# RFID_transmitter_V2.net
KiCad netlist of a schematic drawn in Altium Designer
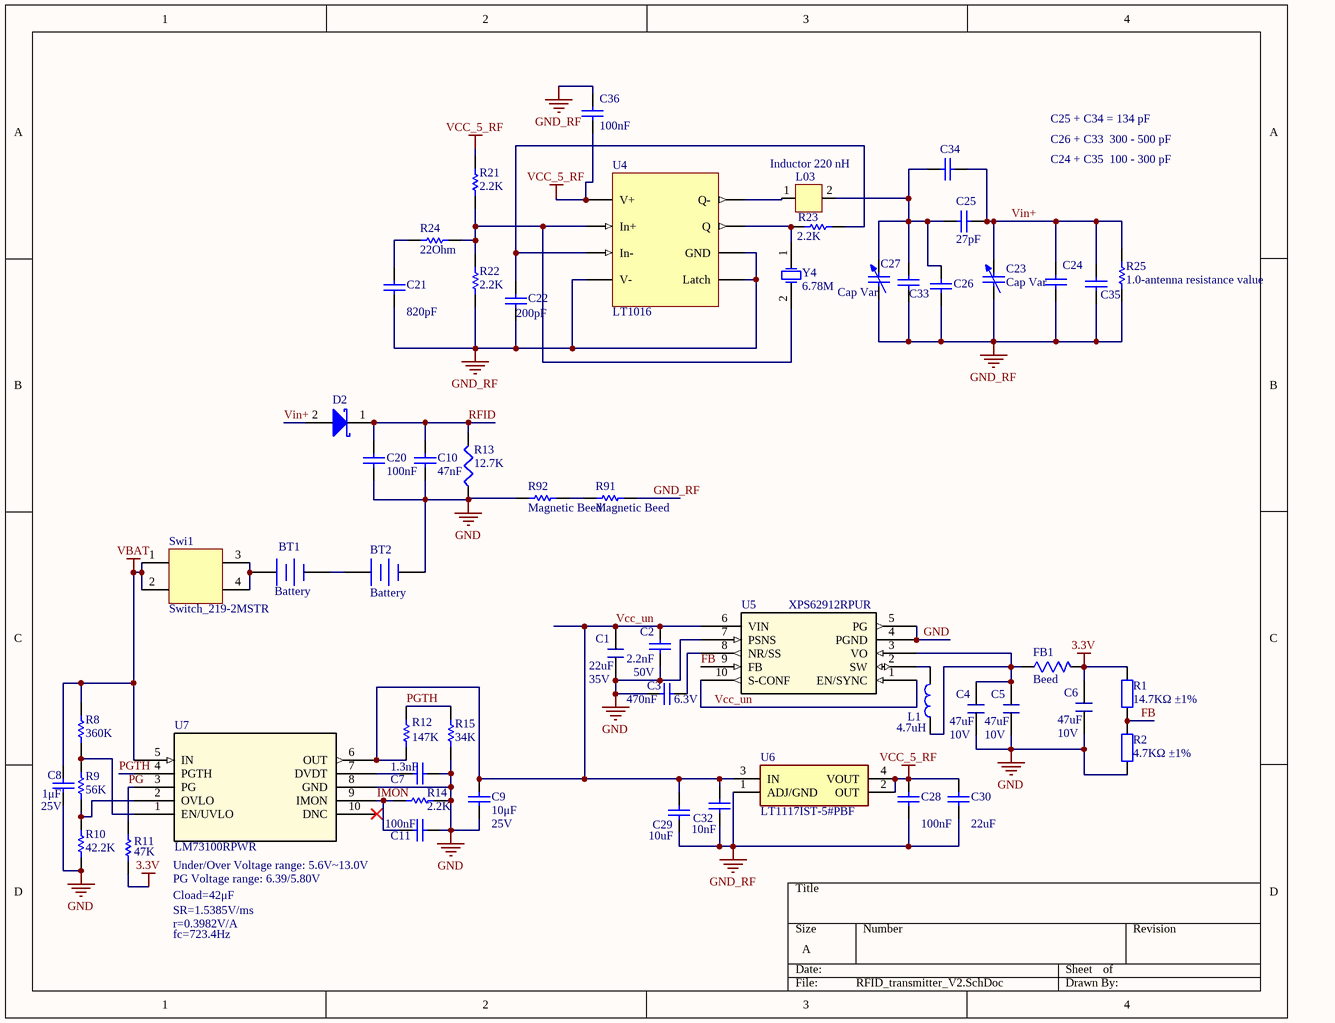
[diagram p0: RFID_transmitter_V2.SchDoc]

(export (version "E")
  (design (tool "Eeschema 10.0.6"))
  (components
    (comp (ref "BT1")
      (value "Battery")
      (footprint "Battery")
      (description "Multicell Battery")
      (fields (field (name "PUBLISHER") "Altium Limited"))
      (libsource (lib "Miscellaneous Devices") (part "Battery"))
    )
    (comp (ref "BT2")
      (value "Battery")
      (footprint "Battery")
      (description "Multicell Battery")
      (fields (field (name "PUBLISHER") "Altium Limited"))
      (libsource (lib "Miscellaneous Devices") (part "Battery"))
    )
    (comp (ref "C1")
      (value "22uF")
      (footprint "C0805")
      (fields
        (field (name "VOLTAGE") "35V")
        (field (name "PART NUMBER") "C2012X5R1V226M125AC")
        (field (name "MANUFACTURER") "TDK")
        (field (name "Comment") "Multilayer Ceramic Capacitor")
      )
      (libsource (lib "Integrated_Library") (part "C-Ceramic"))
    )
    (comp (ref "C2")
      (value "2.2nF")
      (footprint "0402")
      (description "Capacitor (Semiconductor SIM Model)")
      (fields
        (field (name "VOLTAGE") "50V")
        (field (name "PART NUMBER") "GRM155R71H222KA01D")
        (field (name "MANUFACTURER") "MuRata")
        (field (name "PUBLISHER") "Altium Limited")
      )
      (libsource (lib "Miscellaneous Devices") (part "Cap Semi"))
    )
    (comp (ref "C3")
      (value "470nF")
      (footprint "1608[0603]")
      (description "Capacitor (Semiconductor SIM Model)")
      (fields
        (field (name "VOLTAGE") "6.3V")
        (field (name "MANUFACTURER") "MuRata")
        (field (name "PART NUMBER") "GRM188R60J474KA01D")
        (field (name "PUBLISHER") "Altium Limited")
      )
      (libsource (lib "Miscellaneous Devices") (part "Cap Semi"))
    )
    (comp (ref "C4")
      (value "47uF")
      (footprint "C0805")
      (fields
        (field (name "VOLTAGE") "10V")
        (field (name "PART NUMBER") "C2012X5R1A476M125AC")
        (field (name "MANUFACTURER") "TDK")
        (field (name "Comment") "Multilayer Ceramic Capacitor")
      )
      (libsource (lib "Integrated_Library") (part "C-Ceramic"))
    )
    (comp (ref "C5")
      (value "47uF")
      (footprint "C0805")
      (fields
        (field (name "VOLTAGE") "10V")
        (field (name "PART NUMBER") "C2012X5R1A476M125AC")
        (field (name "MANUFACTURER") "TDK")
        (field (name "Comment") "Multilayer Ceramic Capacitor")
      )
      (libsource (lib "Integrated_Library") (part "C-Ceramic"))
    )
    (comp (ref "C6")
      (value "47uF")
      (footprint "C0805")
      (fields
        (field (name "VOLTAGE") "10V")
        (field (name "PART NUMBER") "C2012X5R1A476M125AC")
        (field (name "MANUFACTURER") "TDK")
        (field (name "Comment") "Multilayer Ceramic Capacitor")
      )
      (libsource (lib "Integrated_Library") (part "C-Ceramic"))
    )
    (comp (ref "C7")
      (value "1.3nF")
      (footprint "0402")
      (description "多层陶瓷电容器MLCC - SMD/SMT 1.3nF 50VDC X7R 5% 0402")
      (fields
        (field (name "VOLTAGE") "50V")
        (field (name "PART NUMBER") "GRM155R71H132JA01D")
        (field (name "PUBLISHER") "Altium Limited")
      )
      (libsource (lib "Miscellaneous Devices") (part "Cap Semi"))
    )
    (comp (ref "C8")
      (value "1μF")
      (footprint "0603")
      (description "多层陶瓷电容器MLCC - SMD/SMT 0603 1uF 25V X6S 10%")
      (fields
        (field (name "VOLTAGE") "25V")
        (field (name "MANUFACTURER") "MuRata")
        (field (name "PART NUMBER") "GRM188C81E105KAADD")
        (field (name "PUBLISHER") "Altium Limited")
      )
      (libsource (lib "Miscellaneous Devices") (part "Cap Semi"))
    )
    (comp (ref "C9")
      (value "10μF")
      (footprint "0603")
      (description "多层陶瓷电容器MLCC - SMD/SMT 10UF 25V 10% 0603")
      (fields
        (field (name "VOLTAGE") "25V")
        (field (name "MANUFACTURER") "MuRata")
        (field (name "PART NUMBER") "GRM188R61E106KA73D")
        (field (name "PUBLISHER") "Altium Limited")
      )
      (libsource (lib "Miscellaneous Devices") (part "Cap Semi"))
    )
    (comp (ref "C10")
      (value "47nF")
      (footprint "0603")
      (description "Capacitor")
      (fields
        (field (name "VOLTAGE") "50V")
        (field (name "PART NUMBER") "CL10B473KB8NNNC")
        (field (name "PUBLISHER") "Altium Limited")
      )
      (libsource (lib "Miscellaneous Devices") (part "Cap Semi"))
    )
    (comp (ref "C11")
      (value "100nF")
      (footprint "0402")
      (description "多层陶瓷电容器MLCC - SMD/SMT 100nF 10VDC X5R 5% 0402")
      (fields
        (field (name "VOLTAGE") "10V")
        (field (name "PART NUMBER") "GRM155R61A104JA01D")
        (field (name "PUBLISHER") "Altium Limited")
      )
      (libsource (lib "Miscellaneous Devices") (part "Cap Semi"))
    )
    (comp (ref "C20")
      (value "100nF")
      (footprint "0603")
      (description "Capacitor")
      (fields
        (field (name "VOLTAGE") "50V")
        (field (name "PART NUMBER") "CL10B104KB8NNNC")
        (field (name "PUBLISHER") "Altium Limited")
      )
      (libsource (lib "Miscellaneous Devices") (part "Cap Semi"))
    )
    (comp (ref "C21")
      (value "820pF")
      (footprint "0603")
      (description "Capacitor")
      (fields (field (name "Comment") "Cap 820p") (field (name "PUBLISHER") "Altium Limited"))
      (libsource (lib "Miscellaneous Devices") (part "Cap"))
    )
    (comp (ref "C22")
      (value "200pF")
      (footprint "0603")
      (description "Capacitor")
      (fields (field (name "Comment") "Cap 200p") (field (name "PUBLISHER") "Altium Limited"))
      (libsource (lib "Miscellaneous Devices") (part "Cap"))
    )
    (comp (ref "C23")
      (value "Cap Var")
      (footprint "Variable_Capacitor_JZ400HV1")
      (description "Variable or Adjustable Capacitor")
      (fields (field (name "PUBLISHER") "Altium Limited"))
      (libsource (lib "Miscellaneous Devices") (part "Cap Var"))
    )
    (comp (ref "C24")
      (value "Cap")
      (footprint "0603")
      (description "Capacitor_for resonance")
      (fields (field (name "PUBLISHER") "Altium Limited"))
      (libsource (lib "Miscellaneous Devices") (part "Cap"))
    )
    (comp (ref "C25")
      (value "27pF")
      (footprint "0603")
      (description "Capacitor_for resonance")
      (fields (field (name "Comment") "Cap") (field (name "PUBLISHER") "Altium Limited"))
      (libsource (lib "Miscellaneous Devices") (part "Cap"))
    )
    (comp (ref "C26")
      (value "random value needs carefully address")
      (footprint "0603")
      (description "Capacitor_for resonance")
      (fields (field (name "PUBLISHER") "Altium Limited"))
      (libsource (lib "Miscellaneous Devices") (part "Cap"))
    )
    (comp (ref "C27")
      (value "Cap Var")
      (footprint "Variable_Capacitor_JZ400HV1")
      (description "Variable or Adjustable Capacitor")
      (fields (field (name "PUBLISHER") "Altium Limited"))
      (libsource (lib "Miscellaneous Devices") (part "Cap Var"))
    )
    (comp (ref "C28")
      (value "100nF")
      (footprint "0603")
      (description "多层陶瓷电容器MLCC - SMD/SMT 0.1UF 16V 10% 0603")
      (fields
        (field (name "PART NUMBER") "GCM188R71C104KA37J")
        (field (name "VOLTAGE") "16V")
        (field (name "PUBLISHER") "Altium Limited")
      )
      (libsource (lib "Miscellaneous Devices") (part "Cap"))
    )
    (comp (ref "C29")
      (value "10uF")
      (footprint "0603")
      (description "Capacitor")
      (fields
        (field (name "PART NUMBER") "GRM188R61E106KA73D")
        (field (name "MANUFACTURER") "Murata")
        (field (name "PUBLISHER") "Altium Limited")
      )
      (libsource (lib "Miscellaneous Devices") (part "Cap"))
    )
    (comp (ref "C30")
      (value "22uF")
      (footprint "0603")
      (description "Capacitor")
      (fields (field (name "Comment") "Cap 22u") (field (name "PUBLISHER") "Altium Limited"))
      (libsource (lib "Miscellaneous Devices") (part "Cap"))
    )
    (comp (ref "C32")
      (value "10nF")
      (footprint "0603")
      (description "Capacitor")
      (fields (field (name "Comment") "Cap 10n") (field (name "PUBLISHER") "Altium Limited"))
      (libsource (lib "Miscellaneous Devices") (part "Cap"))
    )
    (comp (ref "C33")
      (value "random value needs carefully address")
      (footprint "0603")
      (description "Capacitor_for resonance")
      (fields (field (name "PUBLISHER") "Altium Limited"))
      (libsource (lib "Miscellaneous Devices") (part "Cap"))
    )
    (comp (ref "C34")
      (value "Cap")
      (footprint "0603")
      (description "Capacitor_for resonance")
      (fields (field (name "PUBLISHER") "Altium Limited"))
      (libsource (lib "Miscellaneous Devices") (part "Cap"))
    )
    (comp (ref "C35")
      (value "Cap")
      (footprint "0603")
      (description "Capacitor_for resonance")
      (fields (field (name "PUBLISHER") "Altium Limited"))
      (libsource (lib "Miscellaneous Devices") (part "Cap"))
    )
    (comp (ref "C36")
      (value "100nF")
      (footprint "C1210")
      (description "Capacitor (Semiconductor SIM Model)")
      (fields
        (field (name "VOLTAGE") "10V")
        (field (name "PART NUMBER") "C3225C0G1H104JT000N")
        (field (name "PUBLISHER") "Altium Limited")
      )
      (libsource (lib "Miscellaneous Devices") (part "Cap Semi"))
    )
    (comp (ref "D2")
      (value "Diode")
      (footprint "SamacSys:SOD3716X135N")
      (description "Surface Mount Schottky Power Rectifier")
      (fields
        (field (name "MANUFACTURER_PART_NUMBER") "MBR0540T1G")
        (field (name "MOUSER PART NUMBER") "863-MBR0540T1G")
      )
      (libsource (lib "SamacSys") (part "MBR0540T1G"))
    )
    (comp (ref "FB1")
      (value "Beed")
      (footprint "SamacSys:BEADC2012X110N")
      (description "Wurth Ferrite Bead")
      (fields (field (name "MANUFACTURER_PART_NUMBER") "782853200"))
      (libsource (lib "SamacSys") (part "782853200"))
    )
    (comp (ref "L1")
      (value "4.7uH")
      (footprint "XGL4030")
      (description "Coilcraft Shielded Power Inductors")
      (fields (field (name "PART NUMBER") "XGL4030-472MEC") (field (name "MANUFACTURER") "Coilcraft"))
      (libsource (lib "Integrated_Library") (part "Inductor"))
    )
    (comp (ref "L03")
      (value "Inductor 220 nH")
      (footprint "Ferrite_bead_0805inch_2012mm")
      (description "220nH")
      (libsource (lib "ferrite_bead") (part "Component_1"))
    )
    (comp (ref "R1")
      (value "14.7KΩ ±1%")
      (footprint "LC-0402_R")
      (description "贴片电阻")
      (fields (field (name "PART NUMBER") "CRCW040214K7FKED") (field (name "MANUFACTURER") "Vishay-Dale"))
      (libsource (lib "Miscellaneous Devices LC") (part "0402 1KΩ (1001) 1%"))
    )
    (comp (ref "R2")
      (value "4.7KΩ ±1%")
      (footprint "LC-0402_R")
      (description "贴片电阻")
      (fields (field (name "PART NUMBER") "CRCW04024K70FKED"))
      (libsource (lib "Miscellaneous Devices LC") (part "0402 1KΩ (1001) 1%"))
    )
    (comp (ref "R8")
      (value "360K")
      (footprint "0402-A")
      (description "Resistor")
      (fields
        (field (name "PART NUMBER") "RC0402FR-07360KL")
        (field (name "MANUFACTURER") "YAGEO")
        (field (name "PUBLISHER") "Altium Limited")
      )
      (libsource (lib "Miscellaneous Devices") (part "Res1"))
    )
    (comp (ref "R9")
      (value "56K")
      (footprint "0402-A")
      (description "Resistor")
      (fields
        (field (name "PART NUMBER") "RC0402FR-0756KL")
        (field (name "MANUFACTURER") "YAGEO")
        (field (name "PUBLISHER") "Altium Limited")
      )
      (libsource (lib "Miscellaneous Devices") (part "Res1"))
    )
    (comp (ref "R10")
      (value "42.2K")
      (footprint "0402-A")
      (description "Resistor")
      (fields
        (field (name "PART NUMBER") "RC0603FR-072K2L")
        (field (name "MANUFACTURER") "YAGEO")
        (field (name "PUBLISHER") "Altium Limited")
      )
      (libsource (lib "Miscellaneous Devices") (part "Res1"))
    )
    (comp (ref "R11")
      (value "47K")
      (footprint "0402-A")
      (description "Resistor")
      (fields
        (field (name "PART NUMBER") "RC0402FR-0747KL")
        (field (name "MANUFACTURER") "YAGEO")
        (field (name "PUBLISHER") "Altium Limited")
      )
      (libsource (lib "Miscellaneous Devices") (part "Res1"))
    )
    (comp (ref "R12")
      (value "147K")
      (footprint "0402-A")
      (description "Resistor")
      (fields
        (field (name "PART NUMBER") "RC0402FR-07147KL")
        (field (name "MANUFACTURER") "YAGEO")
        (field (name "PUBLISHER") "Altium Limited")
      )
      (libsource (lib "Miscellaneous Devices") (part "Res1"))
    )
    (comp (ref "R13")
      (value "12.7K")
      (footprint "J1-0603")
      (description "Resistor")
      (fields
        (field (name "PART NUMBER") "RC0603FR-0712K7L")
        (field (name "MANUFACTURER") "YAGEO")
        (field (name "PUBLISHER") "Altium Limited")
      )
      (libsource (lib "Miscellaneous Devices") (part "Res3"))
    )
    (comp (ref "R14")
      (value "2.2K")
      (footprint "0402-A")
      (description "Resistor")
      (fields
        (field (name "PART NUMBER") "RC0402FR-072K2L")
        (field (name "MANUFACTURER") "YAGEO")
        (field (name "PUBLISHER") "Altium Limited")
      )
      (libsource (lib "Miscellaneous Devices") (part "Res1"))
    )
    (comp (ref "R15")
      (value "34K")
      (footprint "0402-A")
      (description "Resistor")
      (fields
        (field (name "PART NUMBER") "RC0402FR-0734KL")
        (field (name "MANUFACTURER") "YAGEO")
        (field (name "PUBLISHER") "Altium Limited")
      )
      (libsource (lib "Miscellaneous Devices") (part "Res1"))
    )
    (comp (ref "R21")
      (value "2.2K")
      (footprint "J1-0603")
      (description "Resistor")
      (fields
        (field (name "PART NUMBER") "RC0603FR-072K2L")
        (field (name "MANUFACTURER") "YAGEO")
        (field (name "PUBLISHER") "Altium Limited")
      )
      (libsource (lib "Miscellaneous Devices") (part "Res1"))
    )
    (comp (ref "R22")
      (value "2.2K")
      (footprint "J1-0603")
      (description "Resistor")
      (fields
        (field (name "PART NUMBER") "RC0603FR-072K2L")
        (field (name "MANUFACTURER") "YAGEO")
        (field (name "PUBLISHER") "Altium Limited")
      )
      (libsource (lib "Miscellaneous Devices") (part "Res1"))
    )
    (comp (ref "R23")
      (value "2.2K")
      (footprint "J1-0603")
      (description "Resistor")
      (fields
        (field (name "PART NUMBER") "RC0603FR-072K2L")
        (field (name "MANUFACTURER") "YAGEO")
        (field (name "PUBLISHER") "Altium Limited")
      )
      (libsource (lib "Miscellaneous Devices") (part "Res1"))
    )
    (comp (ref "R24")
      (value "22Ohm")
      (footprint "J1-0603")
      (description "Resistor")
      (fields
        (field (name "PART NUMBER") "RC0603FR-0722RL")
        (field (name "MANUFACTURER") "YAGEO")
        (field (name "PUBLISHER") "Altium Limited")
      )
      (libsource (lib "Miscellaneous Devices") (part "Res1"))
    )
    (comp (ref "R25")
      (value "1.0-antenna resistance value")
      (footprint "J1-0603")
      (description "Resistor")
      (fields
        (field (name "PART NUMBER") "RC0603FR-071RL")
        (field (name "MANUFACTURER") "YAGEO")
        (field (name "PUBLISHER") "Altium Limited")
      )
      (libsource (lib "Miscellaneous Devices") (part "Res1"))
    )
    (comp (ref "R91")
      (value "Magnetic Beed")
      (footprint "0603")
      (description "Wurth Magnetic Bead")
      (fields (field (name "PUBLISHER") "Altium Limited"))
      (libsource (lib "Miscellaneous Devices") (part "Res1"))
    )
    (comp (ref "R92")
      (value "Magnetic Beed")
      (footprint "0603")
      (description "Wurth Magnetic Bead")
      (fields (field (name "PUBLISHER") "Altium Limited"))
      (libsource (lib "Miscellaneous Devices") (part "Res1"))
    )
    (comp (ref "Swi1")
      (value "Switch_219-2MSTR")
      (footprint "Switch_219-2MSTR")
      (libsource (lib "Switch_219-2MSTR") (part "Switch_219-2MSTR"))
    )
    (comp (ref "U4") (value "LT1016") (footprint "LT1016_SOIC") (libsource (lib "LT1016") (part "LT1016")))
    (comp (ref "U5")
      (value "XPS62912RPUR")
      (footprint "VQFN-HR10_RPU_TEX")
      (description "No Description Available")
      (fields (field (name "COPYRIGHT") "Copyright (C) 2018 Accelerated Designs. All rights reserved"))
      (libsource (lib "Integrated_Library") (part "XPS62912RPUR"))
    )
    (comp (ref "U6")
      (value "LT1117IST-5#PBF")
      (footprint "SamacSys:SOT230P700X180-4N")
      (libsource (lib "SamacSys") (part "LT1117IST-5#PBF"))
    )
    (comp (ref "U7")
      (value "LM73100RPWR")
      (footprint "VQFN-HR-10_2X2_TEX")
      (description "No Description Available")
      (fields (field (name "COPYRIGHT") "Copyright (C) 2018 Accelerated Designs. All rights reserved"))
      (libsource (lib "Integrated_Library") (part "LM73100RPWR"))
    )
    (comp (ref "Y4")
      (value "CRYSTAL")
      (footprint "HC-49SMD")
      (description "Industry standard SMD crystal")
      (fields
        (field (name "FREQUENCY") "6.78M")
        (field (name "PART NUMBER") "LFXTAL057410Bulk")
        (field (name "MANUFACTURER") "IQD")
      )
      (libsource (lib "Integrated_Library") (part "CRYSTAL"))
    )
  )
  (nets
    (net (code "1") (name "/FB") (class "Default")
      (node (ref "R1") (pin "1") (pinfunction "1_1") (pintype "passive"))
      (node (ref "R2") (pin "2") (pinfunction "2_2") (pintype "passive"))
      (node (ref "U5") (pin "9") (pinfunction "FB_9") (pintype "input"))
    )
    (net (code "2") (name "/IMON") (class "Default")
      (node (ref "C11") (pin "2") (pinfunction "2_2") (pintype "passive"))
      (node (ref "R14") (pin "2") (pinfunction "2_2") (pintype "passive"))
      (node (ref "U7") (pin "9") (pinfunction "IMON_9") (pintype "passive"))
    )
    (net (code "3") (name "/PG") (class "Default")
      (node (ref "R11") (pin "2") (pinfunction "2_2") (pintype "passive"))
      (node (ref "U7") (pin "3") (pinfunction "PG_3") (pintype "passive"))
    )
    (net (code "4") (name "/PGTH") (class "Default")
      (node (ref "R12") (pin "2") (pinfunction "2_2") (pintype "passive"))
      (node (ref "R15") (pin "2") (pinfunction "2_2") (pintype "passive"))
      (node (ref "U7") (pin "4") (pinfunction "PGTH_4") (pintype "passive"))
    )
    (net (code "5") (name "/RFID") (class "Default")
      (node (ref "C10") (pin "1") (pinfunction "1_1") (pintype "passive"))
      (node (ref "C20") (pin "1") (pinfunction "1_1") (pintype "passive"))
      (node (ref "D2") (pin "1") (pinfunction "ANODE_1") (pintype "passive"))
      (node (ref "R13") (pin "2") (pinfunction "2_2") (pintype "passive"))
    )
    (net (code "6") (name "/Vcc_un") (class "Default")
      (node (ref "C1") (pin "2") (pinfunction "2_2") (pintype "passive"))
      (node (ref "C2") (pin "2") (pinfunction "2_2") (pintype "passive"))
      (node (ref "C29") (pin "2") (pinfunction "2_2") (pintype "passive"))
      (node (ref "C32") (pin "2") (pinfunction "2_2") (pintype "passive"))
      (node (ref "C9") (pin "2") (pinfunction "2_2") (pintype "passive"))
      (node (ref "R12") (pin "1") (pinfunction "1_1") (pintype "passive"))
      (node (ref "U5") (pin "1") (pinfunction "EN/SYNC_1") (pintype "input"))
      (node (ref "U5") (pin "10") (pinfunction "S-CONF_10") (pintype "output"))
      (node (ref "U5") (pin "6") (pinfunction "VIN_6") (pintype "power_in"))
      (node (ref "U6") (pin "3") (pinfunction "IN_3") (pintype "passive"))
      (node (ref "U7") (pin "6") (pinfunction "OUT_6") (pintype "output"))
    )
    (net (code "7") (name "/Vin+") (class "Default")
      (node (ref "C23") (pin "2") (pinfunction "2_2") (pintype "passive"))
      (node (ref "C24") (pin "2") (pinfunction "2_2") (pintype "passive"))
      (node (ref "C25") (pin "1") (pinfunction "1_1") (pintype "passive"))
      (node (ref "C34") (pin "1") (pinfunction "1_1") (pintype "passive"))
      (node (ref "C35") (pin "2") (pinfunction "2_2") (pintype "passive"))
      (node (ref "D2") (pin "2") (pinfunction "CATHODE_2") (pintype "passive"))
      (node (ref "R25") (pin "1") (pinfunction "1_1") (pintype "passive"))
    )
    (net (code "8") (name "3.3V") (class "Default")
      (node (ref "C6") (pin "2") (pinfunction "2_2") (pintype "passive"))
      (node (ref "FB1") (pin "2") (pinfunction "2_2") (pintype "passive"))
      (node (ref "R1") (pin "2") (pinfunction "2_2") (pintype "passive"))
      (node (ref "R11") (pin "1") (pinfunction "1_1") (pintype "passive"))
    )
    (net (code "9") (name "GND") (class "Default")
      (node (ref "BT2") (pin "2") (pinfunction "-_2") (pintype "passive"))
      (node (ref "C1") (pin "1") (pinfunction "1_1") (pintype "passive"))
      (node (ref "C10") (pin "2") (pinfunction "2_2") (pintype "passive"))
      (node (ref "C11") (pin "1") (pinfunction "1_1") (pintype "passive"))
      (node (ref "C2") (pin "1") (pinfunction "1_1") (pintype "passive"))
      (node (ref "C20") (pin "2") (pinfunction "2_2") (pintype "passive"))
      (node (ref "C3") (pin "1") (pinfunction "1_1") (pintype "passive"))
      (node (ref "C4") (pin "1") (pinfunction "1_1") (pintype "passive"))
      (node (ref "C5") (pin "1") (pinfunction "1_1") (pintype "passive"))
      (node (ref "C6") (pin "1") (pinfunction "1_1") (pintype "passive"))
      (node (ref "C7") (pin "1") (pinfunction "1_1") (pintype "passive"))
      (node (ref "C8") (pin "1") (pinfunction "1_1") (pintype "passive"))
      (node (ref "C9") (pin "1") (pinfunction "1_1") (pintype "passive"))
      (node (ref "R10") (pin "1") (pinfunction "1_1") (pintype "passive"))
      (node (ref "R13") (pin "1") (pinfunction "1_1") (pintype "passive"))
      (node (ref "R14") (pin "1") (pinfunction "1_1") (pintype "passive"))
      (node (ref "R15") (pin "1") (pinfunction "1_1") (pintype "passive"))
      (node (ref "R2") (pin "1") (pinfunction "1_1") (pintype "passive"))
      (node (ref "R92") (pin "2") (pinfunction "2_2") (pintype "passive"))
      (node (ref "U5") (pin "4") (pinfunction "PGND_4") (pintype "passive"))
      (node (ref "U5") (pin "5") (pinfunction "PG_5") (pintype "output"))
      (node (ref "U5") (pin "7") (pinfunction "PSNS_7") (pintype "input"))
      (node (ref "U7") (pin "8") (pinfunction "GND_8") (pintype "passive"))
    )
    (net (code "10") (name "GND_RF") (class "Default")
      (node (ref "C21") (pin "1") (pinfunction "1_1") (pintype "passive"))
      (node (ref "C22") (pin "1") (pinfunction "1_1") (pintype "passive"))
      (node (ref "C23") (pin "1") (pinfunction "1_1") (pintype "passive"))
      (node (ref "C24") (pin "1") (pinfunction "1_1") (pintype "passive"))
      (node (ref "C26") (pin "2") (pinfunction "2_2") (pintype "passive"))
      (node (ref "C27") (pin "1") (pinfunction "1_1") (pintype "passive"))
      (node (ref "C28") (pin "1") (pinfunction "1_1") (pintype "passive"))
      (node (ref "C29") (pin "1") (pinfunction "1_1") (pintype "passive"))
      (node (ref "C30") (pin "1") (pinfunction "1_1") (pintype "passive"))
      (node (ref "C32") (pin "1") (pinfunction "1_1") (pintype "passive"))
      (node (ref "C33") (pin "2") (pinfunction "2_2") (pintype "passive"))
      (node (ref "C35") (pin "1") (pinfunction "1_1") (pintype "passive"))
      (node (ref "C36") (pin "2") (pinfunction "2_2") (pintype "passive"))
      (node (ref "R22") (pin "1") (pinfunction "1_1") (pintype "passive"))
      (node (ref "R25") (pin "2") (pinfunction "2_2") (pintype "passive"))
      (node (ref "R91") (pin "1") (pinfunction "1_1") (pintype "passive"))
      (node (ref "U4") (pin "4") (pinfunction "V-_4") (pintype "power_in"))
      (node (ref "U4") (pin "5") (pinfunction "Latch_5") (pintype "passive"))
      (node (ref "U4") (pin "6") (pinfunction "GND_6") (pintype "power_in"))
      (node (ref "U6") (pin "1") (pinfunction "ADJ/GND_1") (pintype "passive"))
    )
    (net (code "11") (name "Net-(BT1-+)") (class "Default")
      (node (ref "BT1") (pin "1") (pinfunction "+_1") (pintype "passive"))
      (node (ref "Swi1") (pin "3") (pinfunction "Out1_3") (pintype "power_in"))
      (node (ref "Swi1") (pin "4") (pinfunction "Out2_4") (pintype "power_in"))
    )
    (net (code "12") (name "Net-(BT1--)") (class "Default")
      (node (ref "BT1") (pin "2") (pinfunction "-_2") (pintype "passive"))
      (node (ref "BT2") (pin "1") (pinfunction "+_1") (pintype "passive"))
    )
    (net (code "13") (name "Net-(C21-Pad2)") (class "Default")
      (node (ref "C21") (pin "2") (pinfunction "2_2") (pintype "passive"))
      (node (ref "R24") (pin "2") (pinfunction "2_2") (pintype "passive"))
    )
    (net (code "14") (name "Net-(C25-Pad2)") (class "Default")
      (node (ref "C25") (pin "2") (pinfunction "2_2") (pintype "passive"))
      (node (ref "C26") (pin "1") (pinfunction "1_1") (pintype "passive"))
      (node (ref "C27") (pin "2") (pinfunction "2_2") (pintype "passive"))
      (node (ref "C33") (pin "1") (pinfunction "1_1") (pintype "passive"))
      (node (ref "C34") (pin "2") (pinfunction "2_2") (pintype "passive"))
      (node (ref "L03") (pin "2") (pinfunction "2_2") (pintype "passive"))
    )
    (net (code "15") (name "Net-(R91-Pad2)") (class "Default")
      (node (ref "R91") (pin "2") (pinfunction "2_2") (pintype "passive"))
      (node (ref "R92") (pin "1") (pinfunction "1_1") (pintype "passive"))
    )
    (net (code "16") (name "Net-(U4-In+)") (class "Default")
      (node (ref "R21") (pin "1") (pinfunction "1_1") (pintype "passive"))
      (node (ref "R22") (pin "2") (pinfunction "2_2") (pintype "passive"))
      (node (ref "R24") (pin "1") (pinfunction "1_1") (pintype "passive"))
      (node (ref "U4") (pin "2") (pinfunction "In+_2") (pintype "input"))
      (node (ref "Y4") (pin "2") (pinfunction "OSC2_2") (pintype "passive"))
    )
    (net (code "17") (name "Net-(U4-In-)") (class "Default")
      (node (ref "C22") (pin "2") (pinfunction "2_2") (pintype "passive"))
      (node (ref "R23") (pin "1") (pinfunction "1_1") (pintype "passive"))
      (node (ref "U4") (pin "3") (pinfunction "In-_3") (pintype "input"))
    )
    (net (code "18") (name "Net-(U4-Q)") (class "Default")
      (node (ref "R23") (pin "2") (pinfunction "2_2") (pintype "passive"))
      (node (ref "U4") (pin "7") (pinfunction "Q_7") (pintype "output"))
      (node (ref "Y4") (pin "1") (pinfunction "OSC1_1") (pintype "passive"))
    )
    (net (code "19") (name "Net-(U4-Q-)") (class "Default")
      (node (ref "L03") (pin "1") (pinfunction "1_1") (pintype "passive"))
      (node (ref "U4") (pin "8") (pinfunction "Q-_8") (pintype "output"))
    )
    (net (code "20") (name "Net-(U5-NR{slash}SS)") (class "Default")
      (node (ref "C3") (pin "2") (pinfunction "2_2") (pintype "passive"))
      (node (ref "U5") (pin "8") (pinfunction "NR/SS_8") (pintype "output"))
    )
    (net (code "21") (name "Net-(U5-SW)") (class "Default")
      (node (ref "L1") (pin "2") (pinfunction "2_2") (pintype "passive"))
      (node (ref "U5") (pin "2") (pinfunction "SW_2") (pintype "bidirectional"))
    )
    (net (code "22") (name "Net-(U5-VO)") (class "Default")
      (node (ref "C4") (pin "2") (pinfunction "2_2") (pintype "passive"))
      (node (ref "C5") (pin "2") (pinfunction "2_2") (pintype "passive"))
      (node (ref "FB1") (pin "1") (pinfunction "1_1") (pintype "passive"))
      (node (ref "L1") (pin "1") (pinfunction "1_1") (pintype "passive"))
      (node (ref "U5") (pin "3") (pinfunction "VO_3") (pintype "input"))
    )
    (net (code "23") (name "Net-(U7-DVDT)") (class "Default")
      (node (ref "C7") (pin "2") (pinfunction "2_2") (pintype "passive"))
      (node (ref "U7") (pin "7") (pinfunction "DVDT_7") (pintype "passive"))
    )
    (net (code "24") (name "Net-(U7-EN{slash}UVLO)") (class "Default")
      (node (ref "R8") (pin "1") (pinfunction "1_1") (pintype "passive"))
      (node (ref "R9") (pin "2") (pinfunction "2_2") (pintype "passive"))
      (node (ref "U7") (pin "1") (pinfunction "EN/UVLO_1") (pintype "passive"))
    )
    (net (code "25") (name "Net-(U7-OVLO)") (class "Default")
      (node (ref "R10") (pin "2") (pinfunction "2_2") (pintype "passive"))
      (node (ref "R9") (pin "1") (pinfunction "1_1") (pintype "passive"))
      (node (ref "U7") (pin "2") (pinfunction "OVLO_2") (pintype "passive"))
    )
    (net (code "26") (name "VBAT") (class "Default")
      (node (ref "C8") (pin "2") (pinfunction "2_2") (pintype "passive"))
      (node (ref "R8") (pin "2") (pinfunction "2_2") (pintype "passive"))
      (node (ref "Swi1") (pin "1") (pinfunction "In1_1") (pintype "power_in"))
      (node (ref "Swi1") (pin "2") (pinfunction "In2_2") (pintype "power_in"))
      (node (ref "U7") (pin "5") (pinfunction "IN_5") (pintype "input"))
    )
    (net (code "27") (name "VCC_5_RF") (class "Default")
      (node (ref "C28") (pin "2") (pinfunction "2_2") (pintype "passive"))
      (node (ref "C30") (pin "2") (pinfunction "2_2") (pintype "passive"))
      (node (ref "C36") (pin "1") (pinfunction "1_1") (pintype "passive"))
      (node (ref "R21") (pin "2") (pinfunction "2_2") (pintype "passive"))
      (node (ref "U4") (pin "1") (pinfunction "V+_1") (pintype "passive"))
      (node (ref "U6") (pin "2") (pinfunction "OUT_2") (pintype "passive"))
      (node (ref "U6") (pin "4") (pinfunction "VOUT_4") (pintype "passive"))
    )
    (net (code "28") (name "unconnected-(U7-DNC-Pad10)") (class "Default")
      (node (ref "U7") (pin "10") (pinfunction "DNC_10") (pintype "passive+no_connect"))
    )
  )
)
